# cpu.net
KiCad netlist of a schematic drawn in Altium Designer
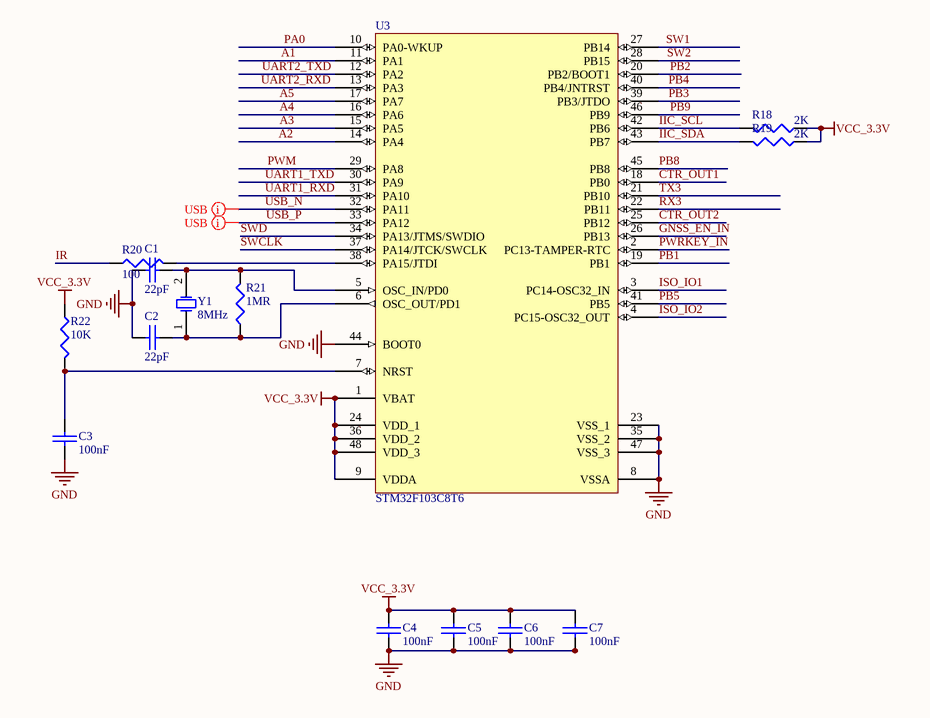
[diagram p0: cpu.SchDoc]

(export (version "E")
  (design (tool "Eeschema 10.0.6"))
  (components
    (comp (ref "C1")
      (value "22pF")
      (footprint "0402C")
      (description "Capacitor")
      (libsource (lib "SM") (part "CAP"))
    )
    (comp (ref "C2")
      (value "22pF")
      (footprint "0402C")
      (description "Capacitor")
      (libsource (lib "SM") (part "CAP"))
    )
    (comp (ref "C3")
      (value "100nF")
      (footprint "0402C")
      (description "Capacitor")
      (libsource (lib "SM") (part "CAP"))
    )
    (comp (ref "C4")
      (value "100nF")
      (footprint "0402C")
      (description "Capacitor")
      (libsource (lib "SM") (part "CAP"))
    )
    (comp (ref "C5")
      (value "100nF")
      (footprint "0402C")
      (description "Capacitor")
      (libsource (lib "SM") (part "CAP"))
    )
    (comp (ref "C6")
      (value "100nF")
      (footprint "0402C")
      (description "Capacitor")
      (libsource (lib "SM") (part "CAP"))
    )
    (comp (ref "C7")
      (value "100nF")
      (footprint "0402C")
      (description "Capacitor")
      (libsource (lib "SM") (part "CAP"))
    )
    (comp (ref "R18")
      (value "2K")
      (footprint "0402R")
      (description "Resistor")
      (fields (field (name "PUBLISHER") "Altium Limited"))
      (libsource (lib "SM") (part "Res3"))
    )
    (comp (ref "R19")
      (value "2K")
      (footprint "0402R")
      (description "Resistor")
      (fields (field (name "PUBLISHER") "Altium Limited"))
      (libsource (lib "SM") (part "Res3"))
    )
    (comp (ref "R20")
      (value "100")
      (footprint "0402R")
      (description "Resistor")
      (fields (field (name "PUBLISHER") "Altium Limited"))
      (libsource (lib "SM") (part "Res3"))
    )
    (comp (ref "R21")
      (value "1MR")
      (footprint "0402R")
      (description "Resistor")
      (fields (field (name "PUBLISHER") "Altium Limited"))
      (libsource (lib "SM") (part "Res3"))
    )
    (comp (ref "R22")
      (value "10K")
      (footprint "0402R")
      (description "Resistor")
      (fields (field (name "PUBLISHER") "Altium Limited"))
      (libsource (lib "SM") (part "Res3"))
    )
    (comp (ref "U3")
      (value "STM32F103C8T6")
      (footprint "TQFP-48")
      (description "STM32 ARM-based 32-bit MCU with 64 Kbytes Flash, 48-pin LQFP, Industrial Temperature")
      (fields (field (name "PUBLISHER") "Altium Limited"))
      (libsource (lib "ST Microcontroller 32-Bit STM32") (part "STM32F103C8T6"))
    )
    (comp (ref "Y1")
      (value "8MHz")
      (footprint "CRAY_5032")
      (description "Crystal Oscillator")
      (fields (field (name "PUBLISHER") "Altium Limited"))
      (libsource (lib "Miscellaneous Devices") (part "XTAL"))
    )
  )
  (nets
    (net (code "1") (name "/A1") (class "Default")
      (node (ref "U3") (pin "11") (pinfunction "PA1_11") (pintype "bidirectional"))
    )
    (net (code "2") (name "/A2") (class "Default")
      (node (ref "U3") (pin "14") (pinfunction "PA4_14") (pintype "bidirectional"))
    )
    (net (code "3") (name "/A3") (class "Default")
      (node (ref "U3") (pin "15") (pinfunction "PA5_15") (pintype "bidirectional"))
    )
    (net (code "4") (name "/A4") (class "Default")
      (node (ref "U3") (pin "16") (pinfunction "PA6_16") (pintype "bidirectional"))
    )
    (net (code "5") (name "/A5") (class "Default")
      (node (ref "U3") (pin "17") (pinfunction "PA7_17") (pintype "bidirectional"))
    )
    (net (code "6") (name "/CTR_OUT1") (class "Default")
      (node (ref "U3") (pin "18") (pinfunction "PB0_18") (pintype "bidirectional"))
    )
    (net (code "7") (name "/CTR_OUT2") (class "Default")
      (node (ref "U3") (pin "25") (pinfunction "PB12_25") (pintype "bidirectional"))
    )
    (net (code "8") (name "/GNSS_EN_IN") (class "Default")
      (node (ref "U3") (pin "26") (pinfunction "PB13_26") (pintype "bidirectional"))
    )
    (net (code "9") (name "/IIC_SCL") (class "Default")
      (node (ref "R18") (pin "2") (pinfunction "2_2") (pintype "passive"))
      (node (ref "U3") (pin "42") (pinfunction "PB6_42") (pintype "bidirectional"))
    )
    (net (code "10") (name "/IIC_SDA") (class "Default")
      (node (ref "R19") (pin "2") (pinfunction "2_2") (pintype "passive"))
      (node (ref "U3") (pin "43") (pinfunction "PB7_43") (pintype "bidirectional"))
    )
    (net (code "11") (name "/IR") (class "Default")
      (node (ref "R20") (pin "1") (pinfunction "1_1") (pintype "passive"))
    )
    (net (code "12") (name "/ISO_IO1") (class "Default")
      (node (ref "U3") (pin "3") (pinfunction "PC14-OSC32_IN_3") (pintype "bidirectional"))
    )
    (net (code "13") (name "/ISO_IO2") (class "Default")
      (node (ref "U3") (pin "4") (pinfunction "PC15-OSC32_OUT_4") (pintype "bidirectional"))
    )
    (net (code "14") (name "/PA0") (class "Default")
      (node (ref "U3") (pin "10") (pinfunction "PA0-WKUP_10") (pintype "bidirectional"))
    )
    (net (code "15") (name "/PB1") (class "Default")
      (node (ref "U3") (pin "19") (pinfunction "PB1_19") (pintype "bidirectional"))
    )
    (net (code "16") (name "/PB2") (class "Default")
      (node (ref "U3") (pin "20") (pinfunction "PB2/BOOT1_20") (pintype "bidirectional"))
    )
    (net (code "17") (name "/PB3") (class "Default")
      (node (ref "U3") (pin "39") (pinfunction "PB3/JTDO_39") (pintype "bidirectional"))
    )
    (net (code "18") (name "/PB4") (class "Default")
      (node (ref "U3") (pin "40") (pinfunction "PB4/JNTRST_40") (pintype "bidirectional"))
    )
    (net (code "19") (name "/PB5") (class "Default")
      (node (ref "U3") (pin "41") (pinfunction "PB5_41") (pintype "bidirectional"))
    )
    (net (code "20") (name "/PB8") (class "Default")
      (node (ref "U3") (pin "45") (pinfunction "PB8_45") (pintype "bidirectional"))
    )
    (net (code "21") (name "/PB9") (class "Default")
      (node (ref "U3") (pin "46") (pinfunction "PB9_46") (pintype "bidirectional"))
    )
    (net (code "22") (name "/PWM") (class "Default")
      (node (ref "U3") (pin "29") (pinfunction "PA8_29") (pintype "bidirectional"))
    )
    (net (code "23") (name "/PWRKEY_IN") (class "Default")
      (node (ref "U3") (pin "2") (pinfunction "PC13-TAMPER-RTC_2") (pintype "bidirectional"))
    )
    (net (code "24") (name "/RX3") (class "Default")
      (node (ref "U3") (pin "22") (pinfunction "PB11_22") (pintype "bidirectional"))
    )
    (net (code "25") (name "/SW1") (class "Default")
      (node (ref "U3") (pin "27") (pinfunction "PB14_27") (pintype "bidirectional"))
    )
    (net (code "26") (name "/SW2") (class "Default")
      (node (ref "U3") (pin "28") (pinfunction "PB15_28") (pintype "bidirectional"))
    )
    (net (code "27") (name "/SWCLK") (class "Default")
      (node (ref "U3") (pin "37") (pinfunction "PA14/JTCK/SWCLK_37") (pintype "bidirectional"))
    )
    (net (code "28") (name "/SWD") (class "Default")
      (node (ref "U3") (pin "34") (pinfunction "PA13/JTMS/SWDIO_34") (pintype "bidirectional"))
    )
    (net (code "29") (name "/TX3") (class "Default")
      (node (ref "U3") (pin "21") (pinfunction "PB10_21") (pintype "bidirectional"))
    )
    (net (code "30") (name "/UART1_RXD") (class "Default")
      (node (ref "U3") (pin "31") (pinfunction "PA10_31") (pintype "bidirectional"))
    )
    (net (code "31") (name "/UART1_TXD") (class "Default")
      (node (ref "U3") (pin "30") (pinfunction "PA9_30") (pintype "bidirectional"))
    )
    (net (code "32") (name "/UART2_RXD") (class "Default")
      (node (ref "U3") (pin "13") (pinfunction "PA3_13") (pintype "bidirectional"))
    )
    (net (code "33") (name "/UART2_TXD") (class "Default")
      (node (ref "U3") (pin "12") (pinfunction "PA2_12") (pintype "bidirectional"))
    )
    (net (code "34") (name "/USB_N") (class "Default")
      (node (ref "U3") (pin "32") (pinfunction "PA11_32") (pintype "bidirectional"))
    )
    (net (code "35") (name "/USB_P") (class "Default")
      (node (ref "U3") (pin "33") (pinfunction "PA12_33") (pintype "bidirectional"))
    )
    (net (code "36") (name "GND") (class "Default")
      (node (ref "C1") (pin "1") (pinfunction "1_1") (pintype "passive"))
      (node (ref "C2") (pin "1") (pinfunction "1_1") (pintype "passive"))
      (node (ref "C3") (pin "1") (pinfunction "1_1") (pintype "passive"))
      (node (ref "C4") (pin "1") (pinfunction "1_1") (pintype "passive"))
      (node (ref "C5") (pin "1") (pinfunction "1_1") (pintype "passive"))
      (node (ref "C6") (pin "1") (pinfunction "1_1") (pintype "passive"))
      (node (ref "C7") (pin "1") (pinfunction "1_1") (pintype "passive"))
      (node (ref "U3") (pin "23") (pinfunction "VSS_1_23") (pintype "power_in"))
      (node (ref "U3") (pin "35") (pinfunction "VSS_2_35") (pintype "power_in"))
      (node (ref "U3") (pin "44") (pinfunction "BOOT0_44") (pintype "input"))
      (node (ref "U3") (pin "47") (pinfunction "VSS_3_47") (pintype "power_in"))
      (node (ref "U3") (pin "8") (pinfunction "VSSA_8") (pintype "power_in"))
    )
    (net (code "37") (name "Net-(U3-NRST)") (class "Default")
      (node (ref "C3") (pin "2") (pinfunction "2_2") (pintype "passive"))
      (node (ref "R22") (pin "2") (pinfunction "2_2") (pintype "passive"))
      (node (ref "U3") (pin "7") (pinfunction "NRST_7") (pintype "bidirectional"))
    )
    (net (code "38") (name "Net-(U3-OSC_IN{slash}PD0)") (class "Default")
      (node (ref "C1") (pin "2") (pinfunction "2_2") (pintype "passive"))
      (node (ref "R21") (pin "2") (pinfunction "2_2") (pintype "passive"))
      (node (ref "U3") (pin "5") (pinfunction "OSC_IN/PD0_5") (pintype "input"))
      (node (ref "Y1") (pin "2") (pinfunction "OSC2_2") (pintype "passive"))
    )
    (net (code "39") (name "Net-(U3-OSC_OUT{slash}PD1)") (class "Default")
      (node (ref "C2") (pin "2") (pinfunction "2_2") (pintype "passive"))
      (node (ref "R21") (pin "1") (pinfunction "1_1") (pintype "passive"))
      (node (ref "U3") (pin "6") (pinfunction "OSC_OUT/PD1_6") (pintype "output"))
      (node (ref "Y1") (pin "1") (pinfunction "OSC1_1") (pintype "passive"))
    )
    (net (code "40") (name "Net-(U3-PA15{slash}JTDI)") (class "Default")
      (node (ref "R20") (pin "2") (pinfunction "2_2") (pintype "passive"))
      (node (ref "U3") (pin "38") (pinfunction "PA15/JTDI_38") (pintype "bidirectional"))
    )
    (net (code "41") (name "VCC_3.3V") (class "Default")
      (node (ref "C4") (pin "2") (pinfunction "2_2") (pintype "passive"))
      (node (ref "C5") (pin "2") (pinfunction "2_2") (pintype "passive"))
      (node (ref "C6") (pin "2") (pinfunction "2_2") (pintype "passive"))
      (node (ref "C7") (pin "2") (pinfunction "2_2") (pintype "passive"))
      (node (ref "R18") (pin "1") (pinfunction "1_1") (pintype "passive"))
      (node (ref "R19") (pin "1") (pinfunction "1_1") (pintype "passive"))
      (node (ref "R22") (pin "1") (pinfunction "1_1") (pintype "passive"))
      (node (ref "U3") (pin "1") (pinfunction "VBAT_1") (pintype "power_in"))
      (node (ref "U3") (pin "24") (pinfunction "VDD_1_24") (pintype "power_in"))
      (node (ref "U3") (pin "36") (pinfunction "VDD_2_36") (pintype "power_in"))
      (node (ref "U3") (pin "48") (pinfunction "VDD_3_48") (pintype "power_in"))
      (node (ref "U3") (pin "9") (pinfunction "VDDA_9") (pintype "power_in"))
    )
  )
)
